# lcdpanel.net
KiCad netlist of a schematic drawn in EAGLE
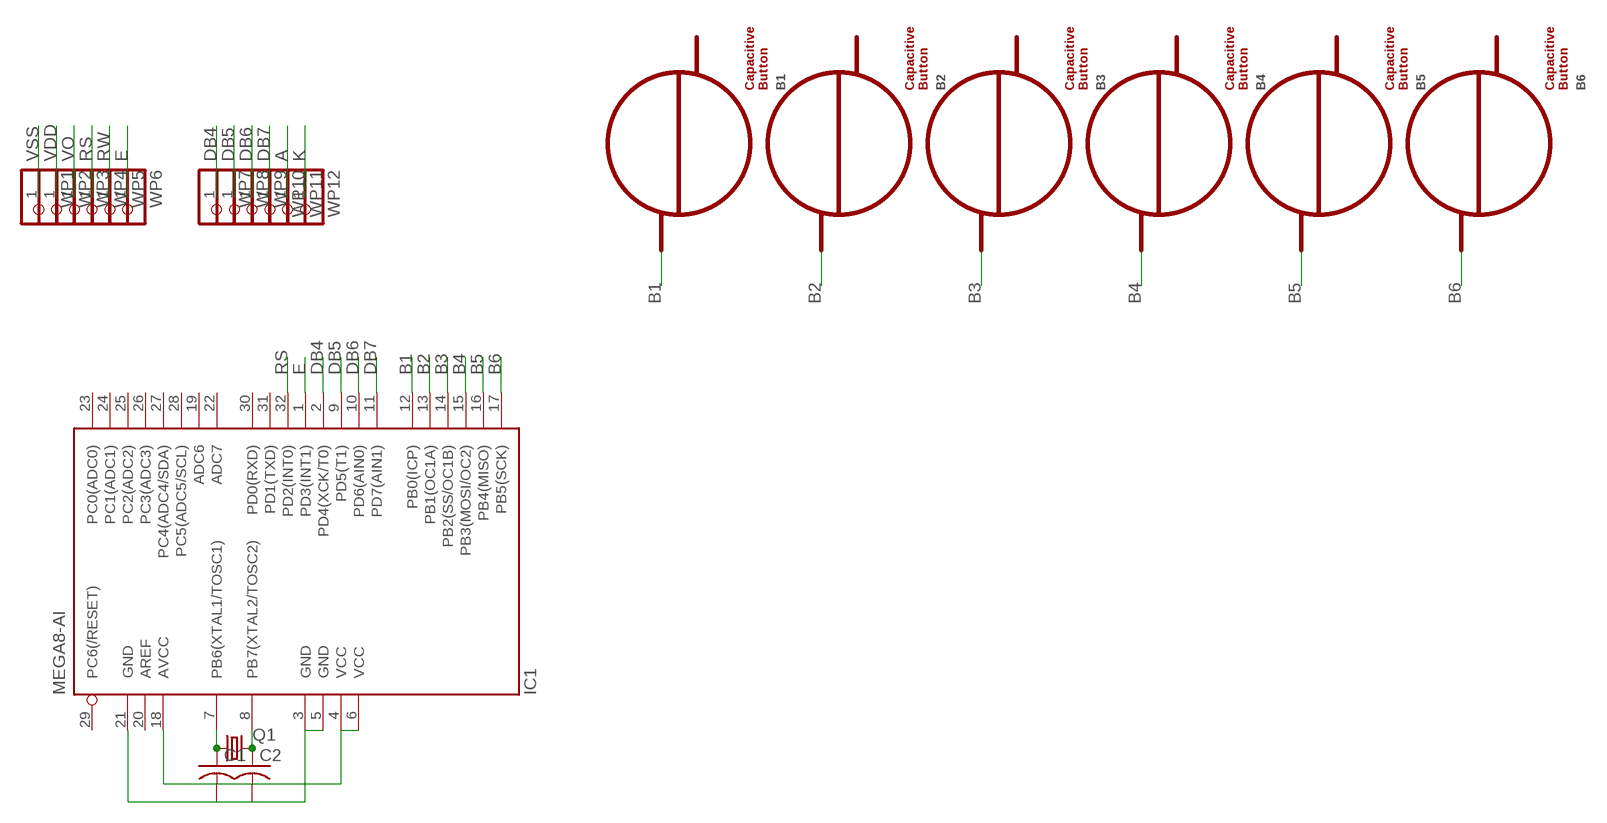
[diagram p0: schematic, sheet 1]

(export (version "E")
  (design (tool "Eeschema 10.0.6"))
  (components
    (comp (ref "B1")
      (value "BUTTON_ACTIVE_DUAL")
      (footprint "eagle-import:BUTTON_ACTIVE_DUAL_10MM")
      (libsource (lib "eagle-import") (part "BUTTON_ACTIVE_DUAL"))
    )
    (comp (ref "B2")
      (value "BUTTON_ACTIVE_DUAL")
      (footprint "eagle-import:BUTTON_ACTIVE_DUAL_10MM")
      (libsource (lib "eagle-import") (part "BUTTON_ACTIVE_DUAL"))
    )
    (comp (ref "B3")
      (value "BUTTON_ACTIVE_DUAL")
      (footprint "eagle-import:BUTTON_ACTIVE_DUAL_10MM")
      (libsource (lib "eagle-import") (part "BUTTON_ACTIVE_DUAL"))
    )
    (comp (ref "B4")
      (value "BUTTON_ACTIVE_DUAL")
      (footprint "eagle-import:BUTTON_ACTIVE_DUAL_10MM")
      (libsource (lib "eagle-import") (part "BUTTON_ACTIVE_DUAL"))
    )
    (comp (ref "B5")
      (value "BUTTON_ACTIVE_DUAL")
      (footprint "eagle-import:BUTTON_ACTIVE_DUAL_10MM")
      (libsource (lib "eagle-import") (part "BUTTON_ACTIVE_DUAL"))
    )
    (comp (ref "B6")
      (value "BUTTON_ACTIVE_DUAL")
      (footprint "eagle-import:BUTTON_ACTIVE_DUAL_10MM")
      (libsource (lib "eagle-import") (part "BUTTON_ACTIVE_DUAL"))
    )
    (comp (ref "C1")
      (value "C-USC1206")
      (footprint "eagle-import:C1206")
      (libsource (lib "eagle-import") (part "C-USC1206"))
    )
    (comp (ref "C2")
      (value "C-USC1206")
      (footprint "eagle-import:C1206")
      (libsource (lib "eagle-import") (part "C-USC1206"))
    )
    (comp (ref "IC1")
      (value "MEGA8-AI")
      (footprint "eagle-import:TQFP32-08")
      (fields (field (name "MPN") "ATMEGA8-16AU"))
      (libsource (lib "eagle-import") (part "MEGA8-AI"))
    )
    (comp (ref "Q1")
      (value "CRYSTALHC49UP")
      (footprint "eagle-import:HC49UP")
      (libsource (lib "eagle-import") (part "CRYSTALHC49UP"))
    )
    (comp (ref "WP1")
      (value "WPAD-1-0805")
      (footprint "eagle-import:WPAD-1-0805")
      (libsource (lib "eagle-import") (part "WPAD-1-0805"))
    )
    (comp (ref "WP2")
      (value "WPAD-1-0805")
      (footprint "eagle-import:WPAD-1-0805")
      (libsource (lib "eagle-import") (part "WPAD-1-0805"))
    )
    (comp (ref "WP3")
      (value "WPAD-1-0805")
      (footprint "eagle-import:WPAD-1-0805")
      (libsource (lib "eagle-import") (part "WPAD-1-0805"))
    )
    (comp (ref "WP4")
      (value "WPAD-1-0805")
      (footprint "eagle-import:WPAD-1-0805")
      (libsource (lib "eagle-import") (part "WPAD-1-0805"))
    )
    (comp (ref "WP5")
      (value "WPAD-1-0805")
      (footprint "eagle-import:WPAD-1-0805")
      (libsource (lib "eagle-import") (part "WPAD-1-0805"))
    )
    (comp (ref "WP6")
      (value "WPAD-1-0805")
      (footprint "eagle-import:WPAD-1-0805")
      (libsource (lib "eagle-import") (part "WPAD-1-0805"))
    )
    (comp (ref "WP7")
      (value "WPAD-1-0805")
      (footprint "eagle-import:WPAD-1-0805")
      (libsource (lib "eagle-import") (part "WPAD-1-0805"))
    )
    (comp (ref "WP8")
      (value "WPAD-1-0805")
      (footprint "eagle-import:WPAD-1-0805")
      (libsource (lib "eagle-import") (part "WPAD-1-0805"))
    )
    (comp (ref "WP9")
      (value "WPAD-1-0805")
      (footprint "eagle-import:WPAD-1-0805")
      (libsource (lib "eagle-import") (part "WPAD-1-0805"))
    )
    (comp (ref "WP10")
      (value "WPAD-1-0805")
      (footprint "eagle-import:WPAD-1-0805")
      (libsource (lib "eagle-import") (part "WPAD-1-0805"))
    )
    (comp (ref "WP11")
      (value "WPAD-1-0805")
      (footprint "eagle-import:WPAD-1-0805")
      (libsource (lib "eagle-import") (part "WPAD-1-0805"))
    )
    (comp (ref "WP12")
      (value "WPAD-1-0805")
      (footprint "eagle-import:WPAD-1-0805")
      (libsource (lib "eagle-import") (part "WPAD-1-0805"))
    )
  )
  (nets
    (net (code "1") (name "/A") (class "Default")
      (node (ref "WP11") (pin "1") (pinfunction "1_1") (pintype "passive"))
    )
    (net (code "2") (name "/B1") (class "Default")
      (node (ref "B1") (pin "Q2") (pinfunction "Q2_Q2") (pintype "passive"))
      (node (ref "IC1") (pin "12") (pinfunction "PB0(ICP)_12") (pintype "bidirectional"))
    )
    (net (code "3") (name "/B2") (class "Default")
      (node (ref "B2") (pin "Q2") (pinfunction "Q2_Q2") (pintype "passive"))
      (node (ref "IC1") (pin "13") (pinfunction "PB1(OC1A)_13") (pintype "bidirectional"))
    )
    (net (code "4") (name "/B3") (class "Default")
      (node (ref "B3") (pin "Q2") (pinfunction "Q2_Q2") (pintype "passive"))
      (node (ref "IC1") (pin "14") (pinfunction "PB2(SS/OC1B)_14") (pintype "bidirectional"))
    )
    (net (code "5") (name "/B4") (class "Default")
      (node (ref "B4") (pin "Q2") (pinfunction "Q2_Q2") (pintype "passive"))
      (node (ref "IC1") (pin "15") (pinfunction "PB3(MOSI/OC2)_15") (pintype "bidirectional"))
    )
    (net (code "6") (name "/B5") (class "Default")
      (node (ref "B5") (pin "Q2") (pinfunction "Q2_Q2") (pintype "passive"))
      (node (ref "IC1") (pin "16") (pinfunction "PB4(MISO)_16") (pintype "bidirectional"))
    )
    (net (code "7") (name "/B6") (class "Default")
      (node (ref "B6") (pin "Q2") (pinfunction "Q2_Q2") (pintype "passive"))
      (node (ref "IC1") (pin "17") (pinfunction "PB5(SCK)_17") (pintype "bidirectional"))
    )
    (net (code "8") (name "/DB4") (class "Default")
      (node (ref "IC1") (pin "2") (pinfunction "PD4(XCK/T0)_2") (pintype "bidirectional"))
      (node (ref "WP7") (pin "1") (pinfunction "1_1") (pintype "passive"))
    )
    (net (code "9") (name "/DB5") (class "Default")
      (node (ref "IC1") (pin "9") (pinfunction "PD5(T1)_9") (pintype "bidirectional"))
      (node (ref "WP8") (pin "1") (pinfunction "1_1") (pintype "passive"))
    )
    (net (code "10") (name "/DB6") (class "Default")
      (node (ref "IC1") (pin "10") (pinfunction "PD6(AIN0)_10") (pintype "bidirectional"))
      (node (ref "WP9") (pin "1") (pinfunction "1_1") (pintype "passive"))
    )
    (net (code "11") (name "/DB7") (class "Default")
      (node (ref "IC1") (pin "11") (pinfunction "PD7(AIN1)_11") (pintype "bidirectional"))
      (node (ref "WP10") (pin "1") (pinfunction "1_1") (pintype "passive"))
    )
    (net (code "12") (name "/E") (class "Default")
      (node (ref "IC1") (pin "1") (pinfunction "PD3(INT1)_1") (pintype "bidirectional"))
      (node (ref "WP6") (pin "1") (pinfunction "1_1") (pintype "passive"))
    )
    (net (code "13") (name "/K") (class "Default")
      (node (ref "WP12") (pin "1") (pinfunction "1_1") (pintype "passive"))
    )
    (net (code "14") (name "/RS") (class "Default")
      (node (ref "IC1") (pin "32") (pinfunction "PD2(INT0)_32") (pintype "bidirectional"))
      (node (ref "WP4") (pin "1") (pinfunction "1_1") (pintype "passive"))
    )
    (net (code "15") (name "/RW") (class "Default")
      (node (ref "WP5") (pin "1") (pinfunction "1_1") (pintype "passive"))
    )
    (net (code "16") (name "/VDD") (class "Default")
      (node (ref "WP2") (pin "1") (pinfunction "1_1") (pintype "passive"))
    )
    (net (code "17") (name "/VO") (class "Default")
      (node (ref "WP3") (pin "1") (pinfunction "1_1") (pintype "passive"))
    )
    (net (code "18") (name "/VSS") (class "Default")
      (node (ref "WP1") (pin "1") (pinfunction "1_1") (pintype "passive"))
    )
    (net (code "19") (name "Net-(C1-Pad2)") (class "Default")
      (node (ref "C1") (pin "2") (pinfunction "2_2") (pintype "passive"))
      (node (ref "C2") (pin "2") (pinfunction "2_2") (pintype "passive"))
      (node (ref "IC1") (pin "21") (pinfunction "GND_21") (pintype "power_in"))
      (node (ref "IC1") (pin "3") (pinfunction "GND_3") (pintype "power_in"))
      (node (ref "IC1") (pin "5") (pinfunction "GND_5") (pintype "power_in"))
    )
    (net (code "20") (name "Net-(IC1-AVCC)") (class "Default")
      (node (ref "IC1") (pin "18") (pinfunction "AVCC_18") (pintype "power_in"))
      (node (ref "IC1") (pin "4") (pinfunction "VCC_4") (pintype "power_in"))
      (node (ref "IC1") (pin "6") (pinfunction "VCC_6") (pintype "power_in"))
    )
    (net (code "21") (name "Net-(IC1-PB6(XTAL1{slash}TOSC1))") (class "Default")
      (node (ref "C1") (pin "1") (pinfunction "1_1") (pintype "passive"))
      (node (ref "IC1") (pin "7") (pinfunction "PB6(XTAL1/TOSC1)_7") (pintype "bidirectional"))
      (node (ref "Q1") (pin "1") (pinfunction "1_1") (pintype "passive"))
    )
    (net (code "22") (name "Net-(IC1-PB7(XTAL2{slash}TOSC2))") (class "Default")
      (node (ref "C2") (pin "1") (pinfunction "1_1") (pintype "passive"))
      (node (ref "IC1") (pin "8") (pinfunction "PB7(XTAL2/TOSC2)_8") (pintype "bidirectional"))
      (node (ref "Q1") (pin "2") (pinfunction "2_2") (pintype "passive"))
    )
    (net (code "23") (name "unconnected-(B1-PadQ1)") (class "Default")
      (node (ref "B1") (pin "Q1") (pinfunction "Q1_Q1") (pintype "passive"))
    )
    (net (code "24") (name "unconnected-(B2-PadQ1)") (class "Default")
      (node (ref "B2") (pin "Q1") (pinfunction "Q1_Q1") (pintype "passive"))
    )
    (net (code "25") (name "unconnected-(B3-PadQ1)") (class "Default")
      (node (ref "B3") (pin "Q1") (pinfunction "Q1_Q1") (pintype "passive"))
    )
    (net (code "26") (name "unconnected-(B4-PadQ1)") (class "Default")
      (node (ref "B4") (pin "Q1") (pinfunction "Q1_Q1") (pintype "passive"))
    )
    (net (code "27") (name "unconnected-(B5-PadQ1)") (class "Default")
      (node (ref "B5") (pin "Q1") (pinfunction "Q1_Q1") (pintype "passive"))
    )
    (net (code "28") (name "unconnected-(B6-PadQ1)") (class "Default")
      (node (ref "B6") (pin "Q1") (pinfunction "Q1_Q1") (pintype "passive"))
    )
    (net (code "29") (name "unconnected-(IC1-ADC6-Pad19)") (class "Default")
      (node (ref "IC1") (pin "19") (pinfunction "ADC6_19") (pintype "bidirectional"))
    )
    (net (code "30") (name "unconnected-(IC1-ADC7-Pad22)") (class "Default")
      (node (ref "IC1") (pin "22") (pinfunction "ADC7_22") (pintype "bidirectional"))
    )
    (net (code "31") (name "unconnected-(IC1-AREF-Pad20)") (class "Default")
      (node (ref "IC1") (pin "20") (pinfunction "AREF_20") (pintype "passive"))
    )
    (net (code "32") (name "unconnected-(IC1-PC0(ADC0)-Pad23)") (class "Default")
      (node (ref "IC1") (pin "23") (pinfunction "PC0(ADC0)_23") (pintype "bidirectional"))
    )
    (net (code "33") (name "unconnected-(IC1-PC1(ADC1)-Pad24)") (class "Default")
      (node (ref "IC1") (pin "24") (pinfunction "PC1(ADC1)_24") (pintype "bidirectional"))
    )
    (net (code "34") (name "unconnected-(IC1-PC2(ADC2)-Pad25)") (class "Default")
      (node (ref "IC1") (pin "25") (pinfunction "PC2(ADC2)_25") (pintype "bidirectional"))
    )
    (net (code "35") (name "unconnected-(IC1-PC3(ADC3)-Pad26)") (class "Default")
      (node (ref "IC1") (pin "26") (pinfunction "PC3(ADC3)_26") (pintype "bidirectional"))
    )
    (net (code "36") (name "unconnected-(IC1-PC4(ADC4{slash}SDA)-Pad27)") (class "Default")
      (node (ref "IC1") (pin "27") (pinfunction "PC4(ADC4/SDA)_27") (pintype "bidirectional"))
    )
    (net (code "37") (name "unconnected-(IC1-PC5(ADC5{slash}SCL)-Pad28)") (class "Default")
      (node (ref "IC1") (pin "28") (pinfunction "PC5(ADC5/SCL)_28") (pintype "bidirectional"))
    )
    (net (code "38") (name "unconnected-(IC1-PC6({slash}RESET)-Pad29)") (class "Default")
      (node (ref "IC1") (pin "29") (pinfunction "PC6(/RESET)_29") (pintype "bidirectional"))
    )
    (net (code "39") (name "unconnected-(IC1-PD0(RXD)-Pad30)") (class "Default")
      (node (ref "IC1") (pin "30") (pinfunction "PD0(RXD)_30") (pintype "bidirectional"))
    )
    (net (code "40") (name "unconnected-(IC1-PD1(TXD)-Pad31)") (class "Default")
      (node (ref "IC1") (pin "31") (pinfunction "PD1(TXD)_31") (pintype "bidirectional"))
    )
  )
)
